# Sensors_Sch.net
KiCad netlist of a schematic drawn in Altium Designer
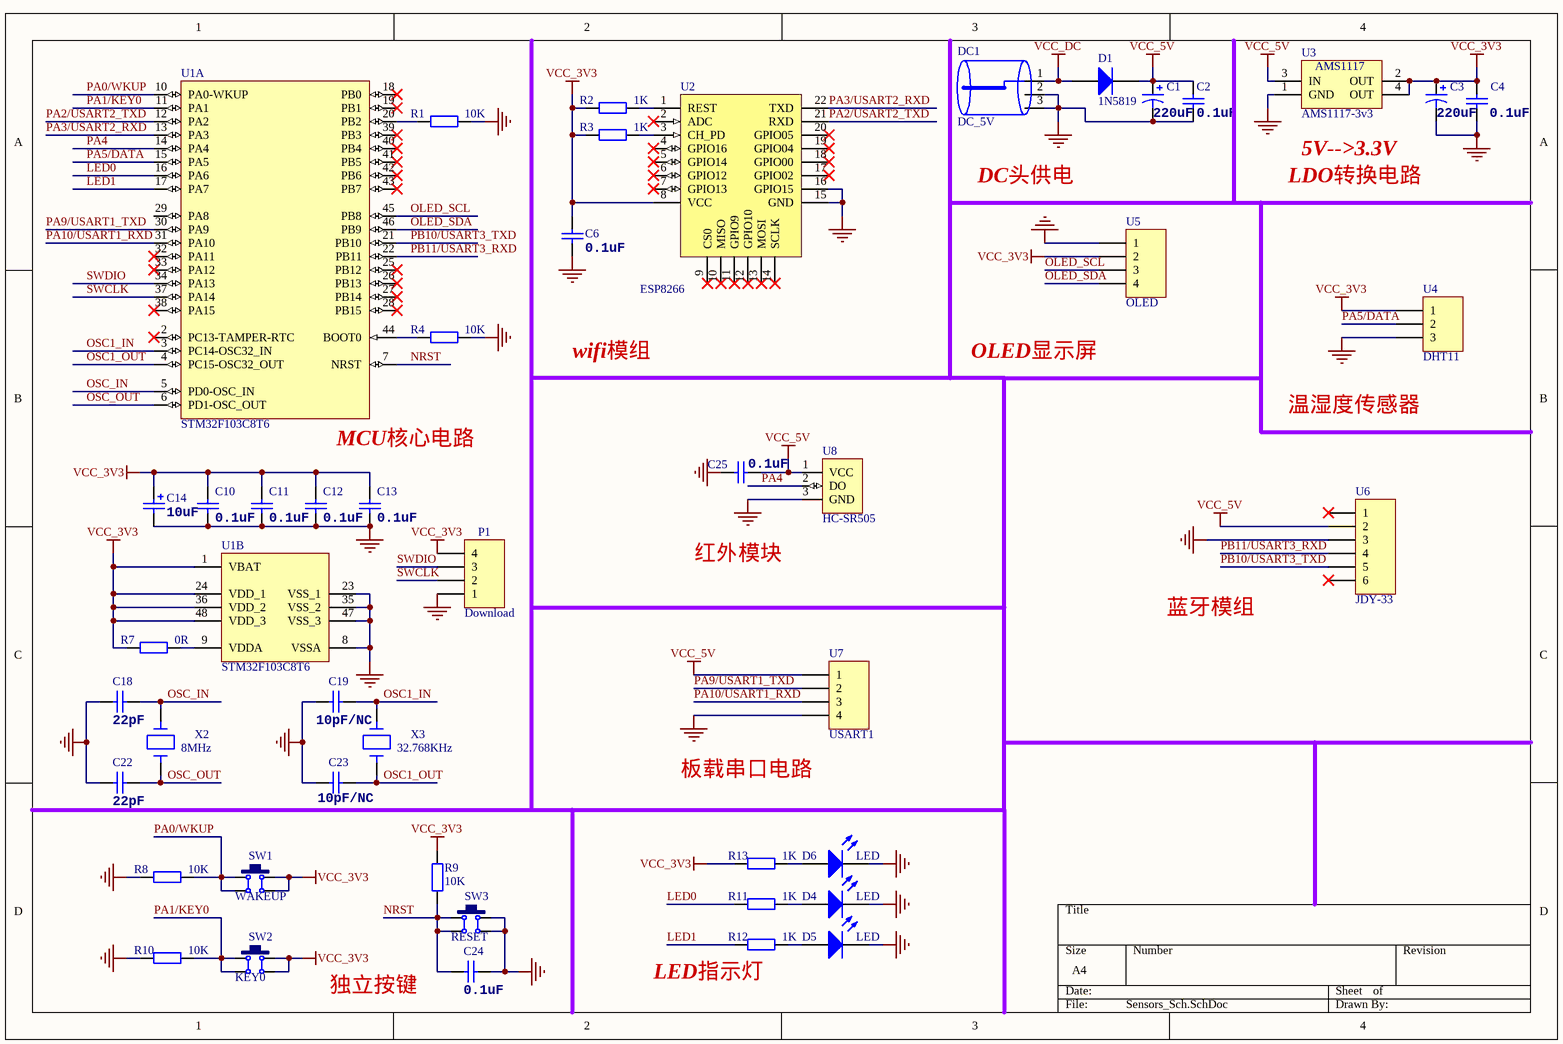
[diagram p0: Sensors_Sch.SchDoc]

(export (version "E")
  (design (tool "Eeschema 10.0.6"))
  (components
    (comp (ref "C1")
      (value "220uF")
      (footprint "C_SMD(6.3x5.3)")
      (description "CAP ALUM POLY 150UF 20% 10V SMD")
      (fields
        (field (name "MANUFACTURER") "KEMET")
        (field (name "MANUFACTURER PART NUMBER") "A765EB157M1ALAE022")
      )
      (libsource (lib "Desiger_Schlib") (part "Cap3"))
    )
    (comp (ref "C2")
      (value "0.1uF")
      (footprint "C0603")
      (description "CAP CER 10000PF 100V X7R 0603")
      (fields
        (field (name "MANUFACTURER") "TDK Corporation")
        (field (name "MANUFACTURER PART NUMBER") "C1608X7R2A103K080AA")
      )
      (libsource (lib "Desiger_Schlib") (part "Cap1"))
    )
    (comp (ref "C3")
      (value "220uF")
      (footprint "C_SMD(6.3x5.3)")
      (description "CAP ALUM POLY 150UF 20% 10V SMD")
      (fields
        (field (name "MANUFACTURER") "KEMET")
        (field (name "MANUFACTURER PART NUMBER") "A765EB157M1ALAE022")
      )
      (libsource (lib "Desiger_Schlib") (part "Cap3"))
    )
    (comp (ref "C4")
      (value "0.1uF")
      (footprint "C0603")
      (description "CAP CER 10000PF 100V X7R 0603")
      (fields
        (field (name "MANUFACTURER") "TDK Corporation")
        (field (name "MANUFACTURER PART NUMBER") "C1608X7R2A103K080AA")
      )
      (libsource (lib "Desiger_Schlib") (part "Cap1"))
    )
    (comp (ref "C6")
      (value "0.1uF")
      (footprint "C0603")
      (description "CAP CER 10000PF 100V X7R 0603")
      (fields
        (field (name "MANUFACTURER") "TDK Corporation")
        (field (name "MANUFACTURER PART NUMBER") "C1608X7R2A103K080AA")
      )
      (libsource (lib "Desiger_Schlib") (part "Cap1"))
    )
    (comp (ref "C10")
      (value "0.1uF")
      (footprint "C0603")
      (description "CAP CER 10000PF 100V X7R 0603")
      (fields
        (field (name "MANUFACTURER") "TDK Corporation")
        (field (name "MANUFACTURER PART NUMBER") "C1608X7R2A103K080AA")
      )
      (libsource (lib "Desiger_Schlib") (part "Cap1"))
    )
    (comp (ref "C11")
      (value "0.1uF")
      (footprint "C0603")
      (description "CAP CER 10000PF 100V X7R 0603")
      (fields
        (field (name "MANUFACTURER") "TDK Corporation")
        (field (name "MANUFACTURER PART NUMBER") "C1608X7R2A103K080AA")
      )
      (libsource (lib "Desiger_Schlib") (part "Cap1"))
    )
    (comp (ref "C12")
      (value "0.1uF")
      (footprint "C0603")
      (description "CAP CER 10000PF 100V X7R 0603")
      (fields
        (field (name "MANUFACTURER") "TDK Corporation")
        (field (name "MANUFACTURER PART NUMBER") "C1608X7R2A103K080AA")
      )
      (libsource (lib "Desiger_Schlib") (part "Cap1"))
    )
    (comp (ref "C13")
      (value "0.1uF")
      (footprint "C0603")
      (description "CAP CER 10000PF 100V X7R 0603")
      (fields
        (field (name "MANUFACTURER") "TDK Corporation")
        (field (name "MANUFACTURER PART NUMBER") "C1608X7R2A103K080AA")
      )
      (libsource (lib "Desiger_Schlib") (part "Cap1"))
    )
    (comp (ref "C14")
      (value "10uF")
      (footprint "TAC1206")
      (description "CAP TANT 10UF 10V 10% 1206")
      (fields
        (field (name "MANUFACTURER") "KEMET")
        (field (name "MANUFACTURER PART NUMBER") "T491A106K010AT7280")
      )
      (libsource (lib "Desiger_Schlib") (part "Cap2"))
    )
    (comp (ref "C18")
      (value "22pF")
      (footprint "C0603")
      (description "CAP CER 10000PF 100V X7R 0603")
      (fields
        (field (name "MANUFACTURER") "TDK Corporation")
        (field (name "MANUFACTURER PART NUMBER") "C1608X7R2A103K080AA")
      )
      (libsource (lib "Desiger_Schlib") (part "Cap1"))
    )
    (comp (ref "C19")
      (value "10pF/NC")
      (footprint "C0603")
      (description "CAP CER 10000PF 100V X7R 0603")
      (fields
        (field (name "MANUFACTURER") "TDK Corporation")
        (field (name "MANUFACTURER PART NUMBER") "C1608X7R2A103K080AA")
      )
      (libsource (lib "Desiger_Schlib") (part "Cap1"))
    )
    (comp (ref "C22")
      (value "22pF")
      (footprint "C0603")
      (description "CAP CER 10000PF 100V X7R 0603")
      (fields
        (field (name "MANUFACTURER") "TDK Corporation")
        (field (name "MANUFACTURER PART NUMBER") "C1608X7R2A103K080AA")
      )
      (libsource (lib "Desiger_Schlib") (part "Cap1"))
    )
    (comp (ref "C23")
      (value "10pF/NC")
      (footprint "C0603")
      (description "CAP CER 10000PF 100V X7R 0603")
      (fields
        (field (name "MANUFACTURER") "TDK Corporation")
        (field (name "MANUFACTURER PART NUMBER") "C1608X7R2A103K080AA")
      )
      (libsource (lib "Desiger_Schlib") (part "Cap1"))
    )
    (comp (ref "C24")
      (value "0.1uF")
      (footprint "C0603")
      (description "CAP CER 10000PF 100V X7R 0603")
      (fields
        (field (name "MANUFACTURER") "TDK Corporation")
        (field (name "MANUFACTURER PART NUMBER") "C1608X7R2A103K080AA")
      )
      (libsource (lib "Desiger_Schlib") (part "Cap1"))
    )
    (comp (ref "C25")
      (value "0.1uF")
      (footprint "C0603")
      (description "CAP CER 10000PF 100V X7R 0603")
      (fields
        (field (name "MANUFACTURER") "TDK Corporation")
        (field (name "MANUFACTURER PART NUMBER") "C1608X7R2A103K080AA")
      )
      (libsource (lib "Desiger_Schlib") (part "Cap1"))
    )
    (comp (ref "D1")
      (value "1N5819")
      (footprint "Desiger_Pcblib:SOD123")
      (description "Default Diode")
      (fields (field (name "PUBLISHER") "Altium Limited"))
      (libsource (lib "Desiger_Schlib") (part "Diode"))
    )
    (comp (ref "D4")
      (value "LED")
      (footprint "LED_0603")
      (description "Typical RED GaAs LED")
      (fields (field (name "PUBLISHER") "Altium Limited"))
      (libsource (lib "Desiger_Schlib") (part "LED"))
    )
    (comp (ref "D5")
      (value "LED")
      (footprint "LED_0603")
      (description "Typical RED GaAs LED")
      (fields (field (name "PUBLISHER") "Altium Limited"))
      (libsource (lib "Desiger_Schlib") (part "LED"))
    )
    (comp (ref "D6")
      (value "LED")
      (footprint "LED_0603")
      (description "Typical RED GaAs LED")
      (fields (field (name "PUBLISHER") "Altium Limited"))
      (libsource (lib "Desiger_Schlib") (part "LED"))
    )
    (comp (ref "DC1")
      (value "DC_5V")
      (footprint "DC_POWER")
      (description "DC005")
      (fields
        (field (name "MANUFACTURER") "TruConnect")
        (field (name "MANUFACTURER PART NUMBER") "K-DC-0052.5")
      )
      (libsource (lib "Desiger_Schlib") (part "DC_5V"))
    )
    (comp (ref "P1")
      (value "Download")
      (footprint "HDR1X4")
      (description "Header, 4-Pin")
      (fields (field (name "PUBLISHER") "Altium Limited"))
      (libsource (lib "") (part "Header 4_1"))
    )
    (comp (ref "R1")
      (value "10K")
      (footprint "R0603")
      (description "贴片电阻")
      (fields (field (name "版权归属") "源创客"))
      (libsource (lib "3.1   - 电阻-电容-电感") (part "R"))
    )
    (comp (ref "R2")
      (value "1K")
      (footprint "R0603")
      (description "贴片电阻")
      (fields (field (name "版权归属") "源创客"))
      (libsource (lib "3.1   - 电阻-电容-电感") (part "R"))
    )
    (comp (ref "R3")
      (value "1K")
      (footprint "R0603")
      (description "贴片电阻")
      (fields (field (name "版权归属") "源创客"))
      (libsource (lib "3.1   - 电阻-电容-电感") (part "R"))
    )
    (comp (ref "R4")
      (value "10K")
      (footprint "R0603")
      (description "贴片电阻")
      (fields (field (name "版权归属") "源创客"))
      (libsource (lib "3.1   - 电阻-电容-电感") (part "R"))
    )
    (comp (ref "R7")
      (value "0R")
      (footprint "R0603")
      (description "贴片电阻")
      (fields (field (name "版权归属") "源创客"))
      (libsource (lib "3.1   - 电阻-电容-电感") (part "R"))
    )
    (comp (ref "R8")
      (value "10K")
      (footprint "R0603")
      (description "贴片电阻")
      (fields (field (name "版权归属") "源创客"))
      (libsource (lib "3.1   - 电阻-电容-电感") (part "R"))
    )
    (comp (ref "R9")
      (value "10K")
      (footprint "R0603")
      (description "贴片电阻")
      (fields (field (name "版权归属") "源创客"))
      (libsource (lib "3.1   - 电阻-电容-电感") (part "R"))
    )
    (comp (ref "R10")
      (value "10K")
      (footprint "R0603")
      (description "贴片电阻")
      (fields (field (name "版权归属") "源创客"))
      (libsource (lib "3.1   - 电阻-电容-电感") (part "R"))
    )
    (comp (ref "R11")
      (value "1K")
      (footprint "R0603")
      (description "贴片电阻")
      (fields (field (name "版权归属") "源创客"))
      (libsource (lib "3.1   - 电阻-电容-电感") (part "R"))
    )
    (comp (ref "R12")
      (value "1K")
      (footprint "R0603")
      (description "贴片电阻")
      (fields (field (name "版权归属") "源创客"))
      (libsource (lib "3.1   - 电阻-电容-电感") (part "R"))
    )
    (comp (ref "R13")
      (value "1K")
      (footprint "R0603")
      (description "贴片电阻")
      (fields (field (name "版权归属") "源创客"))
      (libsource (lib "3.1   - 电阻-电容-电感") (part "R"))
    )
    (comp (ref "SW1")
      (value "WAKEUP")
      (footprint "TSW DIP-6*6*6")
      (description "直插6x6轻触开关")
      (fields (field (name "版权归属") "源创客"))
      (libsource (lib "5.1   - 按键-开关") (part "TSW DIP-6x6"))
    )
    (comp (ref "SW2")
      (value "KEY0")
      (footprint "TSW DIP-6*6*6")
      (description "直插6x6轻触开关")
      (fields (field (name "版权归属") "源创客"))
      (libsource (lib "5.1   - 按键-开关") (part "TSW DIP-6x6"))
    )
    (comp (ref "SW3")
      (value "RESET")
      (footprint "TSW DIP-6*6*6")
      (description "直插6x6轻触开关")
      (fields (field (name "版权归属") "源创客"))
      (libsource (lib "5.1   - 按键-开关") (part "TSW DIP-6x6"))
    )
    (comp (ref "U1")
      (value "STM32F103C8T6")
      (footprint "LQFP48 7X7_N")
      (libsource (lib "") (part "STM32F103C8T6_1"))
    )
    (comp (ref "U2")
      (value "ESP8266")
      (footprint "ESP8266-12E&F")
      (description "ESP8266串口WIFI ESP-12F 无线透传 WIFI模块")
      (libsource (lib "创新实验室51开发板") (part "ESP8266串口WIFI"))
    )
    (comp (ref "U3")
      (value "AMS1117-3v3")
      (footprint "SOT223_L")
      (libsource (lib "Desiger_Schlib") (part "AMS1117-3v3"))
    )
    (comp (ref "U4")
      (value "DHT11")
      (footprint "DHT11_3P")
      (description "Header, 3-Pin")
      (fields (field (name "PUBLISHER") "Altium Limited"))
      (libsource (lib "Miscellaneous Connectors") (part "Header 3"))
    )
    (comp (ref "U5")
      (value "OLED")
      (footprint "OLED_0.96_IIC")
      (description "Header, 4-Pin")
      (fields (field (name "PUBLISHER") "Altium Limited"))
      (libsource (lib "Miscellaneous Connectors") (part "Header 4"))
    )
    (comp (ref "U6")
      (value "JDY-33")
      (footprint "JDY-33")
      (description "Header, 6-Pin")
      (fields (field (name "PUBLISHER") "Altium Limited"))
      (libsource (lib "Miscellaneous Connectors") (part "Header 6"))
    )
    (comp (ref "U7")
      (value "USART1")
      (footprint "HDR1X4")
      (description "Header, 4-Pin")
      (fields (field (name "PUBLISHER") "Altium Limited"))
      (libsource (lib "Miscellaneous Connectors") (part "Header 4"))
    )
    (comp (ref "U8")
      (value "HC-SR505")
      (footprint "HC-SR505")
      (libsource (lib "Desiger_Schlib") (part "HC-SR501"))
    )
    (comp (ref "X2")
      (value "8MHz")
      (footprint "HC-49SMD")
      (description "CRYSTAL 12.0000MHZ 18PF SMD")
      (fields
        (field (name "MANUFACTURER") "Abracon LLC")
        (field (name "MANUFACTURER PART NUMBER") "ABLS-12.000MHZ-B2-T")
      )
      (libsource (lib "Desiger_Schlib") (part "Crystal"))
    )
    (comp (ref "X3")
      (value "32.768KHz")
      (footprint "Crystal_2x6_DIP")
      (description "CRYSTAL 12.0000MHZ 18PF SMD")
      (fields
        (field (name "MANUFACTURER") "Abracon LLC")
        (field (name "MANUFACTURER PART NUMBER") "ABLS-12.000MHZ-B2-T")
      )
      (libsource (lib "Desiger_Schlib") (part "Crystal"))
    )
  )
  (nets
    (net (code "1") (name "/LED0") (class "Default")
      (node (ref "R11") (pin "1") (pinfunction "1_1") (pintype "passive"))
      (node (ref "U1") (pin "16") (pinfunction "PA6_16") (pintype "bidirectional"))
    )
    (net (code "2") (name "/LED1") (class "Default")
      (node (ref "R12") (pin "1") (pinfunction "1_1") (pintype "passive"))
      (node (ref "U1") (pin "17") (pinfunction "PA7_17") (pintype "bidirectional"))
    )
    (net (code "3") (name "/NRST") (class "Default")
      (node (ref "C24") (pin "2") (pinfunction "2_2") (pintype "passive"))
      (node (ref "R9") (pin "1") (pinfunction "1_1") (pintype "passive"))
      (node (ref "SW3") (pin "1") (pinfunction "1_1") (pintype "passive"))
      (node (ref "SW3") (pin "4") (pinfunction "4_4") (pintype "passive"))
      (node (ref "U1") (pin "7") (pinfunction "NRST_7") (pintype "bidirectional"))
    )
    (net (code "4") (name "/OLED_SCL") (class "Default")
      (node (ref "U1") (pin "45") (pinfunction "PB8_45") (pintype "bidirectional"))
      (node (ref "U5") (pin "3") (pinfunction "3_3") (pintype "passive"))
    )
    (net (code "5") (name "/OLED_SDA") (class "Default")
      (node (ref "U1") (pin "46") (pinfunction "PB9_46") (pintype "bidirectional"))
      (node (ref "U5") (pin "4") (pinfunction "4_4") (pintype "passive"))
    )
    (net (code "6") (name "/OSC1_IN") (class "Default")
      (node (ref "C19") (pin "1") (pinfunction "1_1") (pintype "passive"))
      (node (ref "U1") (pin "3") (pinfunction "PC14-OSC32_IN_3") (pintype "bidirectional"))
      (node (ref "X3") (pin "2") (pinfunction "X2_2") (pintype "passive"))
    )
    (net (code "7") (name "/OSC1_OUT") (class "Default")
      (node (ref "C23") (pin "1") (pinfunction "1_1") (pintype "passive"))
      (node (ref "U1") (pin "4") (pinfunction "PC15-OSC32_OUT_4") (pintype "bidirectional"))
      (node (ref "X3") (pin "1") (pinfunction "X1_1") (pintype "passive"))
    )
    (net (code "8") (name "/OSC_IN") (class "Default")
      (node (ref "C18") (pin "1") (pinfunction "1_1") (pintype "passive"))
      (node (ref "U1") (pin "5") (pinfunction "PD0-OSC_IN_5") (pintype "bidirectional"))
      (node (ref "X2") (pin "2") (pinfunction "X2_2") (pintype "passive"))
    )
    (net (code "9") (name "/OSC_OUT") (class "Default")
      (node (ref "C22") (pin "1") (pinfunction "1_1") (pintype "passive"))
      (node (ref "U1") (pin "6") (pinfunction "PD1-OSC_OUT_6") (pintype "bidirectional"))
      (node (ref "X2") (pin "1") (pinfunction "X1_1") (pintype "passive"))
    )
    (net (code "10") (name "/PA0{slash}WKUP") (class "Default")
      (node (ref "R8") (pin "2") (pinfunction "2_2") (pintype "passive"))
      (node (ref "SW1") (pin "1") (pinfunction "1_1") (pintype "passive"))
      (node (ref "SW1") (pin "4") (pinfunction "4_4") (pintype "passive"))
      (node (ref "U1") (pin "10") (pinfunction "PA0-WKUP_10") (pintype "bidirectional"))
    )
    (net (code "11") (name "/PA1{slash}KEY0") (class "Default")
      (node (ref "R10") (pin "2") (pinfunction "2_2") (pintype "passive"))
      (node (ref "SW2") (pin "1") (pinfunction "1_1") (pintype "passive"))
      (node (ref "SW2") (pin "4") (pinfunction "4_4") (pintype "passive"))
      (node (ref "U1") (pin "11") (pinfunction "PA1_11") (pintype "bidirectional"))
    )
    (net (code "12") (name "/PA2{slash}USART2_TXD") (class "Default")
      (node (ref "U1") (pin "12") (pinfunction "PA2_12") (pintype "bidirectional"))
      (node (ref "U2") (pin "21") (pinfunction "RXD_21") (pintype "power_in"))
    )
    (net (code "13") (name "/PA3{slash}USART2_RXD") (class "Default")
      (node (ref "U1") (pin "13") (pinfunction "PA3_13") (pintype "bidirectional"))
      (node (ref "U2") (pin "22") (pinfunction "TXD_22") (pintype "power_in"))
    )
    (net (code "14") (name "/PA4") (class "Default")
      (node (ref "U1") (pin "14") (pinfunction "PA4_14") (pintype "bidirectional"))
      (node (ref "U8") (pin "2") (pinfunction "DO_2") (pintype "bidirectional"))
    )
    (net (code "15") (name "/PA5{slash}DATA") (class "Default")
      (node (ref "U1") (pin "15") (pinfunction "PA5_15") (pintype "bidirectional"))
      (node (ref "U4") (pin "2") (pinfunction "2_2") (pintype "passive"))
    )
    (net (code "16") (name "/PA9{slash}USART1_TXD") (class "Default")
      (node (ref "U1") (pin "30") (pinfunction "PA9_30") (pintype "bidirectional"))
      (node (ref "U7") (pin "2") (pinfunction "2_2") (pintype "passive"))
    )
    (net (code "17") (name "/PA10{slash}USART1_RXD") (class "Default")
      (node (ref "U1") (pin "31") (pinfunction "PA10_31") (pintype "bidirectional"))
      (node (ref "U7") (pin "3") (pinfunction "3_3") (pintype "passive"))
    )
    (net (code "18") (name "/PB10{slash}USART3_TXD") (class "Default")
      (node (ref "U1") (pin "21") (pinfunction "PB10_21") (pintype "bidirectional"))
      (node (ref "U6") (pin "5") (pinfunction "5_5") (pintype "passive"))
    )
    (net (code "19") (name "/PB11{slash}USART3_RXD") (class "Default")
      (node (ref "U1") (pin "22") (pinfunction "PB11_22") (pintype "bidirectional"))
      (node (ref "U6") (pin "4") (pinfunction "4_4") (pintype "passive"))
    )
    (net (code "20") (name "/SWCLK") (class "Default")
      (node (ref "P1") (pin "2") (pinfunction "2_2") (pintype "passive"))
      (node (ref "U1") (pin "37") (pinfunction "PA14_37") (pintype "bidirectional"))
    )
    (net (code "21") (name "/SWDIO") (class "Default")
      (node (ref "P1") (pin "3") (pinfunction "3_3") (pintype "passive"))
      (node (ref "U1") (pin "34") (pinfunction "PA13_34") (pintype "bidirectional"))
    )
    (net (code "22") (name "GND") (class "Default")
      (node (ref "C1") (pin "2") (pinfunction "-_2") (pintype "passive"))
      (node (ref "C10") (pin "1") (pinfunction "1_1") (pintype "passive"))
      (node (ref "C11") (pin "1") (pinfunction "1_1") (pintype "passive"))
      (node (ref "C12") (pin "1") (pinfunction "1_1") (pintype "passive"))
      (node (ref "C13") (pin "1") (pinfunction "1_1") (pintype "passive"))
      (node (ref "C14") (pin "2") (pinfunction "-_2") (pintype "passive"))
      (node (ref "C18") (pin "2") (pinfunction "2_2") (pintype "passive"))
      (node (ref "C19") (pin "2") (pinfunction "2_2") (pintype "passive"))
      (node (ref "C2") (pin "1") (pinfunction "1_1") (pintype "passive"))
      (node (ref "C22") (pin "2") (pinfunction "2_2") (pintype "passive"))
      (node (ref "C23") (pin "2") (pinfunction "2_2") (pintype "passive"))
      (node (ref "C24") (pin "1") (pinfunction "1_1") (pintype "passive"))
      (node (ref "C25") (pin "2") (pinfunction "2_2") (pintype "passive"))
      (node (ref "C3") (pin "2") (pinfunction "-_2") (pintype "passive"))
      (node (ref "C4") (pin "1") (pinfunction "1_1") (pintype "passive"))
      (node (ref "C6") (pin "2") (pinfunction "2_2") (pintype "passive"))
      (node (ref "D4") (pin "2") (pinfunction "K_2") (pintype "passive"))
      (node (ref "D5") (pin "2") (pinfunction "K_2") (pintype "passive"))
      (node (ref "D6") (pin "2") (pinfunction "K_2") (pintype "passive"))
      (node (ref "DC1") (pin "2") (pinfunction "GND_2") (pintype "passive"))
      (node (ref "DC1") (pin "3") (pinfunction "GND_3") (pintype "passive"))
      (node (ref "P1") (pin "1") (pinfunction "1_1") (pintype "passive"))
      (node (ref "R1") (pin "2") (pinfunction "2_2") (pintype "passive"))
      (node (ref "R10") (pin "1") (pinfunction "1_1") (pintype "passive"))
      (node (ref "R4") (pin "2") (pinfunction "2_2") (pintype "passive"))
      (node (ref "R8") (pin "1") (pinfunction "1_1") (pintype "passive"))
      (node (ref "SW3") (pin "2") (pinfunction "2_2") (pintype "passive"))
      (node (ref "SW3") (pin "3") (pinfunction "3_3") (pintype "passive"))
      (node (ref "U1") (pin "23") (pinfunction "VSS_1_23") (pintype "passive"))
      (node (ref "U1") (pin "35") (pinfunction "VSS_2_35") (pintype "passive"))
      (node (ref "U1") (pin "47") (pinfunction "VSS_3_47") (pintype "passive"))
      (node (ref "U1") (pin "8") (pinfunction "VSSA_8") (pintype "passive"))
      (node (ref "U2") (pin "15") (pinfunction "GND_15") (pintype "power_in"))
      (node (ref "U2") (pin "16") (pinfunction "GPIO15_16") (pintype "power_in"))
      (node (ref "U3") (pin "1") (pinfunction "GND_1") (pintype "passive"))
      (node (ref "U4") (pin "3") (pinfunction "3_3") (pintype "passive"))
      (node (ref "U5") (pin "1") (pinfunction "1_1") (pintype "passive"))
      (node (ref "U6") (pin "3") (pinfunction "3_3") (pintype "passive"))
      (node (ref "U7") (pin "4") (pinfunction "4_4") (pintype "passive"))
      (node (ref "U8") (pin "3") (pinfunction "GND_3") (pintype "passive"))
    )
    (net (code "23") (name "Net-(D4-A)") (class "Default")
      (node (ref "D4") (pin "1") (pinfunction "A_1") (pintype "passive"))
      (node (ref "R11") (pin "2") (pinfunction "2_2") (pintype "passive"))
    )
    (net (code "24") (name "Net-(D5-A)") (class "Default")
      (node (ref "D5") (pin "1") (pinfunction "A_1") (pintype "passive"))
      (node (ref "R12") (pin "2") (pinfunction "2_2") (pintype "passive"))
    )
    (net (code "25") (name "Net-(D6-A)") (class "Default")
      (node (ref "D6") (pin "1") (pinfunction "A_1") (pintype "passive"))
      (node (ref "R13") (pin "2") (pinfunction "2_2") (pintype "passive"))
    )
    (net (code "26") (name "Net-(U1A-BOOT0)") (class "Default")
      (node (ref "R4") (pin "1") (pinfunction "1_1") (pintype "passive"))
      (node (ref "U1") (pin "44") (pinfunction "BOOT0_44") (pintype "input"))
    )
    (net (code "27") (name "Net-(U1A-PB2)") (class "Default")
      (node (ref "R1") (pin "1") (pinfunction "1_1") (pintype "passive"))
      (node (ref "U1") (pin "20") (pinfunction "PB2_20") (pintype "bidirectional"))
    )
    (net (code "28") (name "Net-(U1B-VDDA)") (class "Default")
      (node (ref "R7") (pin "2") (pinfunction "2_2") (pintype "passive"))
      (node (ref "U1") (pin "9") (pinfunction "VDDA_9") (pintype "passive"))
    )
    (net (code "29") (name "Net-(U2-CH_PD)") (class "Default")
      (node (ref "R3") (pin "2") (pinfunction "2_2") (pintype "passive"))
      (node (ref "U2") (pin "3") (pinfunction "CH_PD_3") (pintype "input"))
    )
    (net (code "30") (name "Net-(U2-REST)") (class "Default")
      (node (ref "R2") (pin "2") (pinfunction "2_2") (pintype "passive"))
      (node (ref "U2") (pin "1") (pinfunction "REST_1") (pintype "passive"))
    )
    (net (code "31") (name "VCC_3V3") (class "Default")
      (node (ref "C10") (pin "2") (pinfunction "2_2") (pintype "passive"))
      (node (ref "C11") (pin "2") (pinfunction "2_2") (pintype "passive"))
      (node (ref "C12") (pin "2") (pinfunction "2_2") (pintype "passive"))
      (node (ref "C13") (pin "2") (pinfunction "2_2") (pintype "passive"))
      (node (ref "C14") (pin "1") (pinfunction "+_1") (pintype "passive"))
      (node (ref "C3") (pin "1") (pinfunction "+_1") (pintype "passive"))
      (node (ref "C4") (pin "2") (pinfunction "2_2") (pintype "passive"))
      (node (ref "C6") (pin "1") (pinfunction "1_1") (pintype "passive"))
      (node (ref "P1") (pin "4") (pinfunction "4_4") (pintype "passive"))
      (node (ref "R13") (pin "1") (pinfunction "1_1") (pintype "passive"))
      (node (ref "R2") (pin "1") (pinfunction "1_1") (pintype "passive"))
      (node (ref "R3") (pin "1") (pinfunction "1_1") (pintype "passive"))
      (node (ref "R7") (pin "1") (pinfunction "1_1") (pintype "passive"))
      (node (ref "R9") (pin "2") (pinfunction "2_2") (pintype "passive"))
      (node (ref "SW1") (pin "2") (pinfunction "2_2") (pintype "passive"))
      (node (ref "SW1") (pin "3") (pinfunction "3_3") (pintype "passive"))
      (node (ref "SW2") (pin "2") (pinfunction "2_2") (pintype "passive"))
      (node (ref "SW2") (pin "3") (pinfunction "3_3") (pintype "passive"))
      (node (ref "U1") (pin "1") (pinfunction "VBAT_1") (pintype "passive"))
      (node (ref "U1") (pin "24") (pinfunction "VDD_1_24") (pintype "passive"))
      (node (ref "U1") (pin "36") (pinfunction "VDD_2_36") (pintype "passive"))
      (node (ref "U1") (pin "48") (pinfunction "VDD_3_48") (pintype "passive"))
      (node (ref "U2") (pin "8") (pinfunction "VCC_8") (pintype "power_in"))
      (node (ref "U3") (pin "2") (pinfunction "OUT_2") (pintype "passive"))
      (node (ref "U3") (pin "4") (pinfunction "OUT_4") (pintype "passive"))
      (node (ref "U4") (pin "1") (pinfunction "1_1") (pintype "passive"))
      (node (ref "U5") (pin "2") (pinfunction "2_2") (pintype "passive"))
    )
    (net (code "32") (name "VCC_5V") (class "Default")
      (node (ref "C1") (pin "1") (pinfunction "+_1") (pintype "passive"))
      (node (ref "C2") (pin "2") (pinfunction "2_2") (pintype "passive"))
      (node (ref "C25") (pin "1") (pinfunction "1_1") (pintype "passive"))
      (node (ref "D1") (pin "2") (pinfunction "K_2") (pintype "passive"))
      (node (ref "U3") (pin "3") (pinfunction "IN_3") (pintype "passive"))
      (node (ref "U6") (pin "2") (pinfunction "2_2") (pintype "passive"))
      (node (ref "U7") (pin "1") (pinfunction "1_1") (pintype "passive"))
      (node (ref "U8") (pin "1") (pinfunction "VCC_1") (pintype "passive"))
    )
    (net (code "33") (name "VCC_DC") (class "Default")
      (node (ref "D1") (pin "1") (pinfunction "A_1") (pintype "passive"))
      (node (ref "DC1") (pin "1") (pinfunction "VCC_1") (pintype "power_in"))
    )
    (net (code "34") (name "unconnected-(U1A-PA8-Pad29)") (class "Default")
      (node (ref "U1") (pin "29") (pinfunction "PA8_29") (pintype "bidirectional"))
    )
    (net (code "35") (name "unconnected-(U1A-PA11-Pad32)") (class "Default")
      (node (ref "U1") (pin "32") (pinfunction "PA11_32") (pintype "bidirectional+no_connect"))
    )
    (net (code "36") (name "unconnected-(U1A-PA12-Pad33)") (class "Default")
      (node (ref "U1") (pin "33") (pinfunction "PA12_33") (pintype "bidirectional+no_connect"))
    )
    (net (code "37") (name "unconnected-(U1A-PA15-Pad38)") (class "Default")
      (node (ref "U1") (pin "38") (pinfunction "PA15_38") (pintype "bidirectional+no_connect"))
    )
    (net (code "38") (name "unconnected-(U1A-PB0-Pad18)") (class "Default")
      (node (ref "U1") (pin "18") (pinfunction "PB0_18") (pintype "bidirectional+no_connect"))
    )
    (net (code "39") (name "unconnected-(U1A-PB1-Pad19)") (class "Default")
      (node (ref "U1") (pin "19") (pinfunction "PB1_19") (pintype "bidirectional+no_connect"))
    )
    (net (code "40") (name "unconnected-(U1A-PB3-Pad39)") (class "Default")
      (node (ref "U1") (pin "39") (pinfunction "PB3_39") (pintype "bidirectional+no_connect"))
    )
    (net (code "41") (name "unconnected-(U1A-PB4-Pad40)") (class "Default")
      (node (ref "U1") (pin "40") (pinfunction "PB4_40") (pintype "bidirectional+no_connect"))
    )
    (net (code "42") (name "unconnected-(U1A-PB5-Pad41)") (class "Default")
      (node (ref "U1") (pin "41") (pinfunction "PB5_41") (pintype "bidirectional+no_connect"))
    )
    (net (code "43") (name "unconnected-(U1A-PB6-Pad42)") (class "Default")
      (node (ref "U1") (pin "42") (pinfunction "PB6_42") (pintype "bidirectional+no_connect"))
    )
    (net (code "44") (name "unconnected-(U1A-PB7-Pad43)") (class "Default")
      (node (ref "U1") (pin "43") (pinfunction "PB7_43") (pintype "bidirectional+no_connect"))
    )
    (net (code "45") (name "unconnected-(U1A-PB12-Pad25)") (class "Default")
      (node (ref "U1") (pin "25") (pinfunction "PB12_25") (pintype "bidirectional+no_connect"))
    )
    (net (code "46") (name "unconnected-(U1A-PB13-Pad26)") (class "Default")
      (node (ref "U1") (pin "26") (pinfunction "PB13_26") (pintype "bidirectional+no_connect"))
    )
    (net (code "47") (name "unconnected-(U1A-PB14-Pad27)") (class "Default")
      (node (ref "U1") (pin "27") (pinfunction "PB14_27") (pintype "bidirectional+no_connect"))
    )
    (net (code "48") (name "unconnected-(U1A-PB15-Pad28)") (class "Default")
      (node (ref "U1") (pin "28") (pinfunction "PB15_28") (pintype "bidirectional+no_connect"))
    )
    (net (code "49") (name "unconnected-(U1A-PC13-TAMPER-RTC-Pad2)") (class "Default")
      (node (ref "U1") (pin "2") (pinfunction "PC13-TAMPER-RTC_2") (pintype "bidirectional+no_connect"))
    )
    (net (code "50") (name "unconnected-(U2-ADC-Pad2)") (class "Default")
      (node (ref "U2") (pin "2") (pinfunction "ADC_2") (pintype "input+no_connect"))
    )
    (net (code "51") (name "unconnected-(U2-CS0-Pad9)") (class "Default")
      (node (ref "U2") (pin "9") (pinfunction "CS0_9") (pintype "power_in+no_connect"))
    )
    (net (code "52") (name "unconnected-(U2-GPIO00-Pad18)") (class "Default")
      (node (ref "U2") (pin "18") (pinfunction "GPIO00_18") (pintype "power_in+no_connect"))
    )
    (net (code "53") (name "unconnected-(U2-GPIO02-Pad17)") (class "Default")
      (node (ref "U2") (pin "17") (pinfunction "GPIO02_17") (pintype "power_in+no_connect"))
    )
    (net (code "54") (name "unconnected-(U2-GPIO04-Pad19)") (class "Default")
      (node (ref "U2") (pin "19") (pinfunction "GPIO04_19") (pintype "power_in+no_connect"))
    )
    (net (code "55") (name "unconnected-(U2-GPIO05-Pad20)") (class "Default")
      (node (ref "U2") (pin "20") (pinfunction "GPIO05_20") (pintype "power_in+no_connect"))
    )
    (net (code "56") (name "unconnected-(U2-GPIO9-Pad11)") (class "Default")
      (node (ref "U2") (pin "11") (pinfunction "GPIO9_11") (pintype "power_in+no_connect"))
    )
    (net (code "57") (name "unconnected-(U2-GPIO10-Pad12)") (class "Default")
      (node (ref "U2") (pin "12") (pinfunction "GPIO10_12") (pintype "power_in+no_connect"))
    )
    (net (code "58") (name "unconnected-(U2-GPIO12-Pad6)") (class "Default")
      (node (ref "U2") (pin "6") (pinfunction "GPIO12_6") (pintype "bidirectional+no_connect"))
    )
    (net (code "59") (name "unconnected-(U2-GPIO13-Pad7)") (class "Default")
      (node (ref "U2") (pin "7") (pinfunction "GPIO13_7") (pintype "bidirectional+no_connect"))
    )
    (net (code "60") (name "unconnected-(U2-GPIO14-Pad5)") (class "Default")
      (node (ref "U2") (pin "5") (pinfunction "GPIO14_5") (pintype "bidirectional+no_connect"))
    )
    (net (code "61") (name "unconnected-(U2-GPIO16-Pad4)") (class "Default")
      (node (ref "U2") (pin "4") (pinfunction "GPIO16_4") (pintype "bidirectional+no_connect"))
    )
    (net (code "62") (name "unconnected-(U2-MISO-Pad10)") (class "Default")
      (node (ref "U2") (pin "10") (pinfunction "MISO_10") (pintype "power_in+no_connect"))
    )
    (net (code "63") (name "unconnected-(U2-MOSI-Pad13)") (class "Default")
      (node (ref "U2") (pin "13") (pinfunction "MOSI_13") (pintype "power_in+no_connect"))
    )
    (net (code "64") (name "unconnected-(U2-SCLK-Pad14)") (class "Default")
      (node (ref "U2") (pin "14") (pinfunction "SCLK_14") (pintype "power_in+no_connect"))
    )
    (net (code "65") (name "unconnected-(U6-Pad1)") (class "Default")
      (node (ref "U6") (pin "1") (pinfunction "1_1") (pintype "passive+no_connect"))
    )
    (net (code "66") (name "unconnected-(U6-Pad6)") (class "Default")
      (node (ref "U6") (pin "6") (pinfunction "6_6") (pintype "passive+no_connect"))
    )
  )
)
